# InterfaceBoardRevD.net
KiCad netlist of a schematic drawn in EAGLE
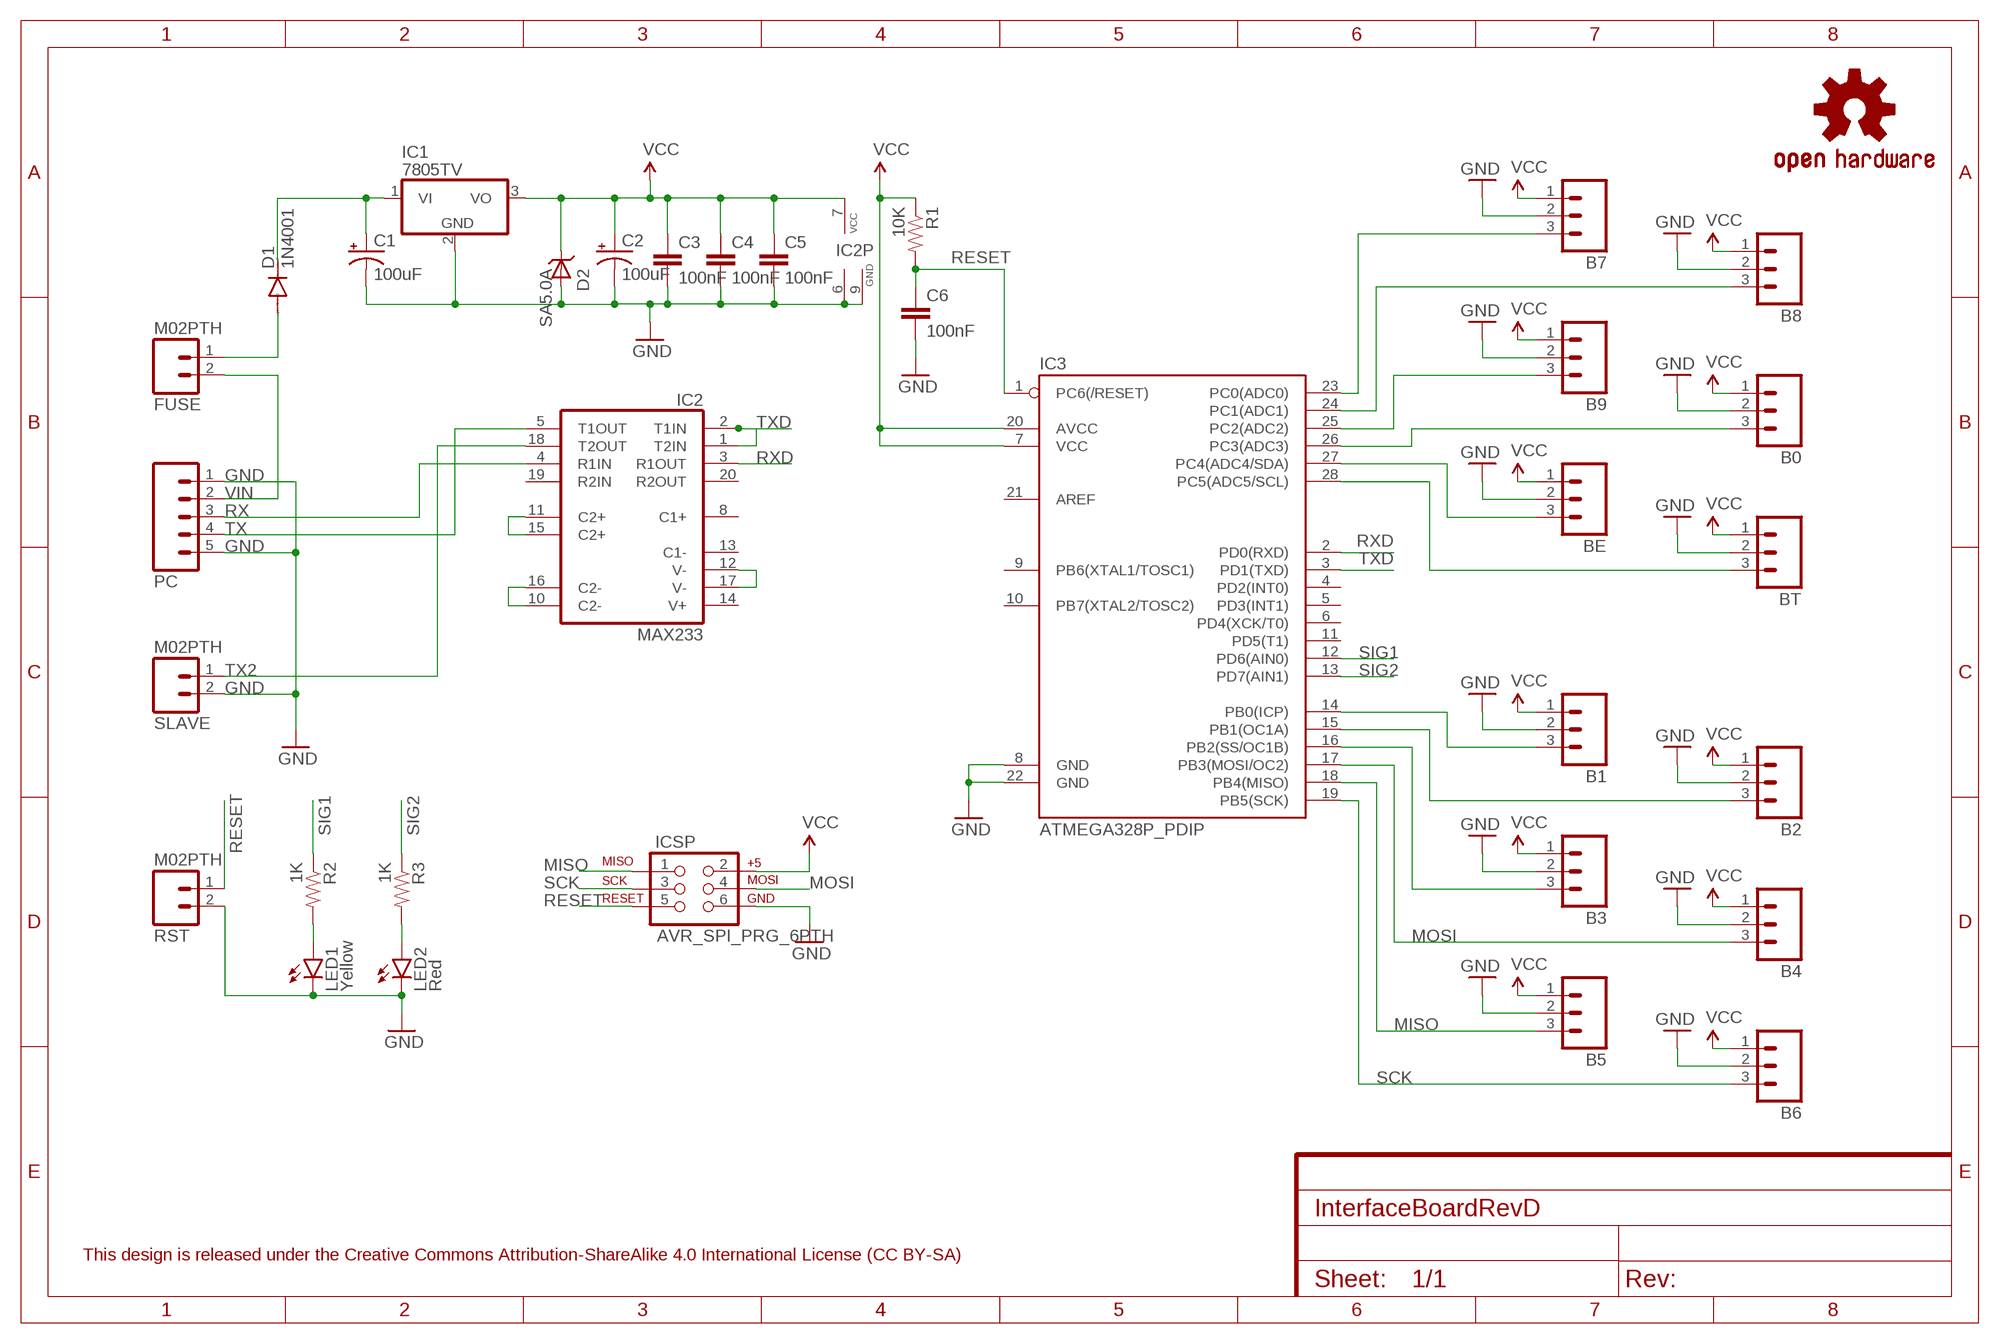
[diagram p0: schematic, sheet 1]

(export (version "E")
  (design (tool "Eeschema 10.0.6"))
  (components
    (comp (ref "B0")
      (value "M03PTH")
      (footprint "eagle-import:1X03")
      (libsource (lib "eagle-import") (part "M03PTH"))
    )
    (comp (ref "B1")
      (value "M03PTH")
      (footprint "eagle-import:1X03")
      (libsource (lib "eagle-import") (part "M03PTH"))
    )
    (comp (ref "B2")
      (value "M03PTH")
      (footprint "eagle-import:1X03")
      (libsource (lib "eagle-import") (part "M03PTH"))
    )
    (comp (ref "B3")
      (value "M03PTH")
      (footprint "eagle-import:1X03")
      (libsource (lib "eagle-import") (part "M03PTH"))
    )
    (comp (ref "B4")
      (value "M03PTH")
      (footprint "eagle-import:1X03")
      (libsource (lib "eagle-import") (part "M03PTH"))
    )
    (comp (ref "B5")
      (value "M03PTH")
      (footprint "eagle-import:1X03")
      (libsource (lib "eagle-import") (part "M03PTH"))
    )
    (comp (ref "B6")
      (value "M03PTH")
      (footprint "eagle-import:1X03")
      (libsource (lib "eagle-import") (part "M03PTH"))
    )
    (comp (ref "B7")
      (value "M03PTH")
      (footprint "eagle-import:1X03")
      (libsource (lib "eagle-import") (part "M03PTH"))
    )
    (comp (ref "B8")
      (value "M03PTH")
      (footprint "eagle-import:1X03")
      (libsource (lib "eagle-import") (part "M03PTH"))
    )
    (comp (ref "B9")
      (value "M03PTH")
      (footprint "eagle-import:1X03")
      (libsource (lib "eagle-import") (part "M03PTH"))
    )
    (comp (ref "BE")
      (value "M03PTH")
      (footprint "eagle-import:1X03")
      (libsource (lib "eagle-import") (part "M03PTH"))
    )
    (comp (ref "BT")
      (value "M03PTH")
      (footprint "eagle-import:1X03")
      (libsource (lib "eagle-import") (part "M03PTH"))
    )
    (comp (ref "C1")
      (value "100uF")
      (footprint "eagle-import:CPOL-RADIAL-100UF-25V")
      (libsource (lib "eagle-import") (part "CAP_POLPTH1"))
    )
    (comp (ref "C2")
      (value "100uF")
      (footprint "eagle-import:CPOL-RADIAL-100UF-25V")
      (libsource (lib "eagle-import") (part "CAP_POLPTH1"))
    )
    (comp (ref "C3")
      (value "100nF")
      (footprint "eagle-import:CAP-PTH-SMALL")
      (libsource (lib "eagle-import") (part "CAPPTH"))
    )
    (comp (ref "C4")
      (value "100nF")
      (footprint "eagle-import:CAP-PTH-SMALL")
      (libsource (lib "eagle-import") (part "CAPPTH"))
    )
    (comp (ref "C5")
      (value "100nF")
      (footprint "eagle-import:CAP-PTH-SMALL")
      (libsource (lib "eagle-import") (part "CAPPTH"))
    )
    (comp (ref "C6")
      (value "100nF")
      (footprint "eagle-import:CAP-PTH-SMALL")
      (libsource (lib "eagle-import") (part "CAPPTH"))
    )
    (comp (ref "D1")
      (value "1N4001")
      (footprint "eagle-import:DO41_DIODE")
      (libsource (lib "eagle-import") (part "1N4001"))
    )
    (comp (ref "D2")
      (value "SA5.0A")
      (footprint "eagle-import:DO41_TVS_UNI")
      (libsource (lib "eagle-import") (part "SA5.0A"))
    )
    (comp (ref "FUSE")
      (value "M02PTH")
      (footprint "eagle-import:1X02")
      (libsource (lib "eagle-import") (part "M02PTH"))
    )
    (comp (ref "IC1")
      (value "7805TV")
      (footprint "eagle-import:TO220V")
      (libsource (lib "eagle-import") (part "78TV05"))
    )
    (comp (ref "IC2")
      (value "MAX233")
      (footprint "eagle-import:DIL20")
      (fields (field (name "MPN") "MAX233ACPP+G36"))
      (libsource (lib "eagle-import") (part "MAX233"))
    )
    (comp (ref "IC3")
      (value "ATMEGA328P_PDIP")
      (footprint "eagle-import:DIL28-3")
      (libsource (lib "eagle-import") (part "ATMEGA328P_PDIP"))
    )
    (comp (ref "ICSP")
      (value "AVR_SPI_PRG_6PTH")
      (footprint "eagle-import:2X3")
      (libsource (lib "eagle-import") (part "AVR_SPI_PRG_6PTH"))
    )
    (comp (ref "LED1")
      (value "Yellow")
      (footprint "eagle-import:LED3MM_LARGEHOLES")
      (libsource (lib "eagle-import") (part "LED-LH3MM"))
    )
    (comp (ref "LED2")
      (value "Red")
      (footprint "eagle-import:LED3MM_LARGEHOLES")
      (libsource (lib "eagle-import") (part "LED-LH3MM"))
    )
    (comp (ref "LOGO1")
      (value "OSHW-LOGOS")
      (footprint "eagle-import:OSHW-LOGO-S")
      (libsource (lib "eagle-import") (part "OSHW-LOGOS"))
    )
    (comp (ref "PC")
      (value "M05PTH")
      (footprint "eagle-import:1X05")
      (libsource (lib "eagle-import") (part "M05PTH"))
    )
    (comp (ref "R1")
      (value "10K")
      (footprint "eagle-import:AXIAL-0.4")
      (libsource (lib "eagle-import") (part "RESISTORPTH-1/4W"))
    )
    (comp (ref "R2")
      (value "1K")
      (footprint "eagle-import:AXIAL-0.4")
      (libsource (lib "eagle-import") (part "RESISTORPTH-1/4W"))
    )
    (comp (ref "R3")
      (value "1K")
      (footprint "eagle-import:AXIAL-0.4")
      (libsource (lib "eagle-import") (part "RESISTORPTH-1/4W"))
    )
    (comp (ref "RST")
      (value "M02PTH")
      (footprint "eagle-import:1X02")
      (libsource (lib "eagle-import") (part "M02PTH"))
    )
    (comp (ref "SLAVE")
      (value "M02PTH")
      (footprint "eagle-import:1X02")
      (libsource (lib "eagle-import") (part "M02PTH"))
    )
  )
  (nets
    (net (code "1") (name "/MISO") (class "Default")
      (node (ref "B5") (pin "3") (pinfunction "3_3") (pintype "passive"))
      (node (ref "IC3") (pin "18") (pinfunction "PB4(MISO)_18") (pintype "bidirectional"))
      (node (ref "ICSP") (pin "1") (pinfunction "1_1") (pintype "passive"))
    )
    (net (code "2") (name "/MOSI") (class "Default")
      (node (ref "B4") (pin "3") (pinfunction "3_3") (pintype "passive"))
      (node (ref "IC3") (pin "17") (pinfunction "PB3(MOSI/OC2)_17") (pintype "bidirectional"))
      (node (ref "ICSP") (pin "4") (pinfunction "4_4") (pintype "passive"))
    )
    (net (code "3") (name "/RESET") (class "Default")
      (node (ref "C6") (pin "1") (pinfunction "1_1") (pintype "passive"))
      (node (ref "IC3") (pin "1") (pinfunction "PC6(/RESET)_1") (pintype "bidirectional"))
      (node (ref "ICSP") (pin "5") (pinfunction "5_5") (pintype "passive"))
      (node (ref "R1") (pin "P$2") (pinfunction "2_P$2") (pintype "passive"))
      (node (ref "RST") (pin "1") (pinfunction "1_1") (pintype "passive"))
    )
    (net (code "4") (name "/RX") (class "Default")
      (node (ref "IC2") (pin "4") (pinfunction "R1IN_4") (pintype "input"))
      (node (ref "PC") (pin "3") (pinfunction "3_3") (pintype "passive"))
    )
    (net (code "5") (name "/RXD") (class "Default")
      (node (ref "IC2") (pin "3") (pinfunction "R1OUT_3") (pintype "output"))
      (node (ref "IC3") (pin "2") (pinfunction "PD0(RXD)_2") (pintype "bidirectional"))
    )
    (net (code "6") (name "/SCK") (class "Default")
      (node (ref "B6") (pin "3") (pinfunction "3_3") (pintype "passive"))
      (node (ref "IC3") (pin "19") (pinfunction "PB5(SCK)_19") (pintype "bidirectional"))
      (node (ref "ICSP") (pin "3") (pinfunction "3_3") (pintype "passive"))
    )
    (net (code "7") (name "/SIG1") (class "Default")
      (node (ref "IC3") (pin "12") (pinfunction "PD6(AIN0)_12") (pintype "bidirectional"))
      (node (ref "R2") (pin "P$1") (pinfunction "1_P$1") (pintype "passive"))
    )
    (net (code "8") (name "/SIG2") (class "Default")
      (node (ref "IC3") (pin "13") (pinfunction "PD7(AIN1)_13") (pintype "bidirectional"))
      (node (ref "R3") (pin "P$1") (pinfunction "1_P$1") (pintype "passive"))
    )
    (net (code "9") (name "/TX") (class "Default")
      (node (ref "IC2") (pin "5") (pinfunction "T1OUT_5") (pintype "output"))
      (node (ref "PC") (pin "4") (pinfunction "4_4") (pintype "passive"))
    )
    (net (code "10") (name "/TX2") (class "Default")
      (node (ref "IC2") (pin "18") (pinfunction "T2OUT_18") (pintype "output"))
      (node (ref "SLAVE") (pin "1") (pinfunction "1_1") (pintype "passive"))
    )
    (net (code "11") (name "/TXD") (class "Default")
      (node (ref "IC2") (pin "1") (pinfunction "T2IN_1") (pintype "input"))
      (node (ref "IC2") (pin "2") (pinfunction "T1IN_2") (pintype "input"))
      (node (ref "IC3") (pin "3") (pinfunction "PD1(TXD)_3") (pintype "bidirectional"))
    )
    (net (code "12") (name "/VIN") (class "Default")
      (node (ref "FUSE") (pin "2") (pinfunction "2_2") (pintype "passive"))
      (node (ref "PC") (pin "2") (pinfunction "2_2") (pintype "passive"))
    )
    (net (code "13") (name "GND") (class "Default")
      (node (ref "B0") (pin "2") (pinfunction "2_2") (pintype "passive"))
      (node (ref "B1") (pin "2") (pinfunction "2_2") (pintype "passive"))
      (node (ref "B2") (pin "2") (pinfunction "2_2") (pintype "passive"))
      (node (ref "B3") (pin "2") (pinfunction "2_2") (pintype "passive"))
      (node (ref "B4") (pin "2") (pinfunction "2_2") (pintype "passive"))
      (node (ref "B5") (pin "2") (pinfunction "2_2") (pintype "passive"))
      (node (ref "B6") (pin "2") (pinfunction "2_2") (pintype "passive"))
      (node (ref "B7") (pin "2") (pinfunction "2_2") (pintype "passive"))
      (node (ref "B8") (pin "2") (pinfunction "2_2") (pintype "passive"))
      (node (ref "B9") (pin "2") (pinfunction "2_2") (pintype "passive"))
      (node (ref "BE") (pin "2") (pinfunction "2_2") (pintype "passive"))
      (node (ref "BT") (pin "2") (pinfunction "2_2") (pintype "passive"))
      (node (ref "C1") (pin "2") (pinfunction "-_2") (pintype "passive"))
      (node (ref "C2") (pin "2") (pinfunction "-_2") (pintype "passive"))
      (node (ref "C3") (pin "2") (pinfunction "2_2") (pintype "passive"))
      (node (ref "C4") (pin "2") (pinfunction "2_2") (pintype "passive"))
      (node (ref "C5") (pin "2") (pinfunction "2_2") (pintype "passive"))
      (node (ref "C6") (pin "2") (pinfunction "2_2") (pintype "passive"))
      (node (ref "D2") (pin "ANODE") (pinfunction "ANODE_ANODE") (pintype "passive"))
      (node (ref "IC1") (pin "2") (pinfunction "GND_2") (pintype "passive"))
      (node (ref "IC2") (pin "6") (pinfunction "GND_6") (pintype "power_in"))
      (node (ref "IC2") (pin "9") (pinfunction "GND_9") (pintype "power_in"))
      (node (ref "IC3") (pin "22") (pinfunction "GND_22") (pintype "bidirectional"))
      (node (ref "IC3") (pin "8") (pinfunction "GND_8") (pintype "bidirectional"))
      (node (ref "ICSP") (pin "6") (pinfunction "6_6") (pintype "passive"))
      (node (ref "LED1") (pin "K") (pinfunction "C_K") (pintype "passive"))
      (node (ref "LED2") (pin "K") (pinfunction "C_K") (pintype "passive"))
      (node (ref "PC") (pin "1") (pinfunction "1_1") (pintype "passive"))
      (node (ref "PC") (pin "5") (pinfunction "5_5") (pintype "passive"))
      (node (ref "RST") (pin "2") (pinfunction "2_2") (pintype "passive"))
      (node (ref "SLAVE") (pin "2") (pinfunction "2_2") (pintype "passive"))
    )
    (net (code "14") (name "Net-(C1-+)") (class "Default")
      (node (ref "C1") (pin "1") (pinfunction "+_1") (pintype "passive"))
      (node (ref "D1") (pin "C") (pinfunction "C_C") (pintype "passive"))
      (node (ref "IC1") (pin "1") (pinfunction "VI_1") (pintype "input"))
    )
    (net (code "15") (name "Net-(D1-PadA)") (class "Default")
      (node (ref "D1") (pin "A") (pinfunction "A_A") (pintype "passive"))
      (node (ref "FUSE") (pin "1") (pinfunction "1_1") (pintype "passive"))
    )
    (net (code "16") (name "Net-(IC2A-C2+-Pad11)") (class "Default")
      (node (ref "IC2") (pin "11") (pinfunction "C2+_11") (pintype "bidirectional"))
      (node (ref "IC2") (pin "15") (pinfunction "C2+_15") (pintype "bidirectional"))
    )
    (net (code "17") (name "Net-(IC2A-C2--Pad10)") (class "Default")
      (node (ref "IC2") (pin "10") (pinfunction "C2-_10") (pintype "bidirectional"))
      (node (ref "IC2") (pin "16") (pinfunction "C2-_16") (pintype "bidirectional"))
    )
    (net (code "18") (name "Net-(IC2A-V--Pad12)") (class "Default")
      (node (ref "IC2") (pin "12") (pinfunction "V-_12") (pintype "bidirectional"))
      (node (ref "IC2") (pin "17") (pinfunction "V-_17") (pintype "bidirectional"))
    )
    (net (code "19") (name "Net-(IC3-PB0(ICP))") (class "Default")
      (node (ref "B1") (pin "3") (pinfunction "3_3") (pintype "passive"))
      (node (ref "IC3") (pin "14") (pinfunction "PB0(ICP)_14") (pintype "bidirectional"))
    )
    (net (code "20") (name "Net-(IC3-PB1(OC1A))") (class "Default")
      (node (ref "B2") (pin "3") (pinfunction "3_3") (pintype "passive"))
      (node (ref "IC3") (pin "15") (pinfunction "PB1(OC1A)_15") (pintype "bidirectional"))
    )
    (net (code "21") (name "Net-(IC3-PB2(SS{slash}OC1B))") (class "Default")
      (node (ref "B3") (pin "3") (pinfunction "3_3") (pintype "passive"))
      (node (ref "IC3") (pin "16") (pinfunction "PB2(SS/OC1B)_16") (pintype "bidirectional"))
    )
    (net (code "22") (name "Net-(IC3-PC0(ADC0))") (class "Default")
      (node (ref "B7") (pin "3") (pinfunction "3_3") (pintype "passive"))
      (node (ref "IC3") (pin "23") (pinfunction "PC0(ADC0)_23") (pintype "bidirectional"))
    )
    (net (code "23") (name "Net-(IC3-PC1(ADC1))") (class "Default")
      (node (ref "B8") (pin "3") (pinfunction "3_3") (pintype "passive"))
      (node (ref "IC3") (pin "24") (pinfunction "PC1(ADC1)_24") (pintype "bidirectional"))
    )
    (net (code "24") (name "Net-(IC3-PC2(ADC2))") (class "Default")
      (node (ref "B9") (pin "3") (pinfunction "3_3") (pintype "passive"))
      (node (ref "IC3") (pin "25") (pinfunction "PC2(ADC2)_25") (pintype "bidirectional"))
    )
    (net (code "25") (name "Net-(IC3-PC3(ADC3))") (class "Default")
      (node (ref "B0") (pin "3") (pinfunction "3_3") (pintype "passive"))
      (node (ref "IC3") (pin "26") (pinfunction "PC3(ADC3)_26") (pintype "bidirectional"))
    )
    (net (code "26") (name "Net-(IC3-PC4(ADC4{slash}SDA))") (class "Default")
      (node (ref "BE") (pin "3") (pinfunction "3_3") (pintype "passive"))
      (node (ref "IC3") (pin "27") (pinfunction "PC4(ADC4/SDA)_27") (pintype "bidirectional"))
    )
    (net (code "27") (name "Net-(IC3-PC5(ADC5{slash}SCL))") (class "Default")
      (node (ref "BT") (pin "3") (pinfunction "3_3") (pintype "passive"))
      (node (ref "IC3") (pin "28") (pinfunction "PC5(ADC5/SCL)_28") (pintype "bidirectional"))
    )
    (net (code "28") (name "Net-(R2-2)") (class "Default")
      (node (ref "LED1") (pin "A") (pinfunction "A_A") (pintype "passive"))
      (node (ref "R2") (pin "P$2") (pinfunction "2_P$2") (pintype "passive"))
    )
    (net (code "29") (name "Net-(R3-2)") (class "Default")
      (node (ref "LED2") (pin "A") (pinfunction "A_A") (pintype "passive"))
      (node (ref "R3") (pin "P$2") (pinfunction "2_P$2") (pintype "passive"))
    )
    (net (code "30") (name "VCC") (class "Default")
      (node (ref "B0") (pin "1") (pinfunction "1_1") (pintype "passive"))
      (node (ref "B1") (pin "1") (pinfunction "1_1") (pintype "passive"))
      (node (ref "B2") (pin "1") (pinfunction "1_1") (pintype "passive"))
      (node (ref "B3") (pin "1") (pinfunction "1_1") (pintype "passive"))
      (node (ref "B4") (pin "1") (pinfunction "1_1") (pintype "passive"))
      (node (ref "B5") (pin "1") (pinfunction "1_1") (pintype "passive"))
      (node (ref "B6") (pin "1") (pinfunction "1_1") (pintype "passive"))
      (node (ref "B7") (pin "1") (pinfunction "1_1") (pintype "passive"))
      (node (ref "B8") (pin "1") (pinfunction "1_1") (pintype "passive"))
      (node (ref "B9") (pin "1") (pinfunction "1_1") (pintype "passive"))
      (node (ref "BE") (pin "1") (pinfunction "1_1") (pintype "passive"))
      (node (ref "BT") (pin "1") (pinfunction "1_1") (pintype "passive"))
      (node (ref "C2") (pin "1") (pinfunction "+_1") (pintype "passive"))
      (node (ref "C3") (pin "1") (pinfunction "1_1") (pintype "passive"))
      (node (ref "C4") (pin "1") (pinfunction "1_1") (pintype "passive"))
      (node (ref "C5") (pin "1") (pinfunction "1_1") (pintype "passive"))
      (node (ref "D2") (pin "CATHODE") (pinfunction "CATHODE_CATHODE") (pintype "passive"))
      (node (ref "IC1") (pin "3") (pinfunction "VO_3") (pintype "passive"))
      (node (ref "IC2") (pin "7") (pinfunction "VCC_7") (pintype "power_in"))
      (node (ref "IC3") (pin "20") (pinfunction "AVCC_20") (pintype "bidirectional"))
      (node (ref "IC3") (pin "7") (pinfunction "VCC_7") (pintype "bidirectional"))
      (node (ref "ICSP") (pin "2") (pinfunction "2_2") (pintype "passive"))
      (node (ref "R1") (pin "P$1") (pinfunction "1_P$1") (pintype "passive"))
    )
    (net (code "31") (name "unconnected-(IC2A-C1+-Pad8)") (class "Default")
      (node (ref "IC2") (pin "8") (pinfunction "C1+_8") (pintype "bidirectional"))
    )
    (net (code "32") (name "unconnected-(IC2A-C1--Pad13)") (class "Default")
      (node (ref "IC2") (pin "13") (pinfunction "C1-_13") (pintype "bidirectional"))
    )
    (net (code "33") (name "unconnected-(IC2A-R2IN-Pad19)") (class "Default")
      (node (ref "IC2") (pin "19") (pinfunction "R2IN_19") (pintype "input"))
    )
    (net (code "34") (name "unconnected-(IC2A-R2OUT-Pad20)") (class "Default")
      (node (ref "IC2") (pin "20") (pinfunction "R2OUT_20") (pintype "output"))
    )
    (net (code "35") (name "unconnected-(IC2A-V+-Pad14)") (class "Default")
      (node (ref "IC2") (pin "14") (pinfunction "V+_14") (pintype "bidirectional"))
    )
    (net (code "36") (name "unconnected-(IC3-AREF-Pad21)") (class "Default")
      (node (ref "IC3") (pin "21") (pinfunction "AREF_21") (pintype "bidirectional"))
    )
    (net (code "37") (name "unconnected-(IC3-PB6(XTAL1{slash}TOSC1)-Pad9)") (class "Default")
      (node (ref "IC3") (pin "9") (pinfunction "PB6(XTAL1/TOSC1)_9") (pintype "bidirectional"))
    )
    (net (code "38") (name "unconnected-(IC3-PB7(XTAL2{slash}TOSC2)-Pad10)") (class "Default")
      (node (ref "IC3") (pin "10") (pinfunction "PB7(XTAL2/TOSC2)_10") (pintype "bidirectional"))
    )
    (net (code "39") (name "unconnected-(IC3-PD2(INT0)-Pad4)") (class "Default")
      (node (ref "IC3") (pin "4") (pinfunction "PD2(INT0)_4") (pintype "bidirectional"))
    )
    (net (code "40") (name "unconnected-(IC3-PD3(INT1)-Pad5)") (class "Default")
      (node (ref "IC3") (pin "5") (pinfunction "PD3(INT1)_5") (pintype "bidirectional"))
    )
    (net (code "41") (name "unconnected-(IC3-PD4(XCK{slash}T0)-Pad6)") (class "Default")
      (node (ref "IC3") (pin "6") (pinfunction "PD4(XCK/T0)_6") (pintype "bidirectional"))
    )
    (net (code "42") (name "unconnected-(IC3-PD5(T1)-Pad11)") (class "Default")
      (node (ref "IC3") (pin "11") (pinfunction "PD5(T1)_11") (pintype "bidirectional"))
    )
  )
)
